# blackfin_a_sdram.net
KiCad netlist of a schematic drawn in Altium Designer
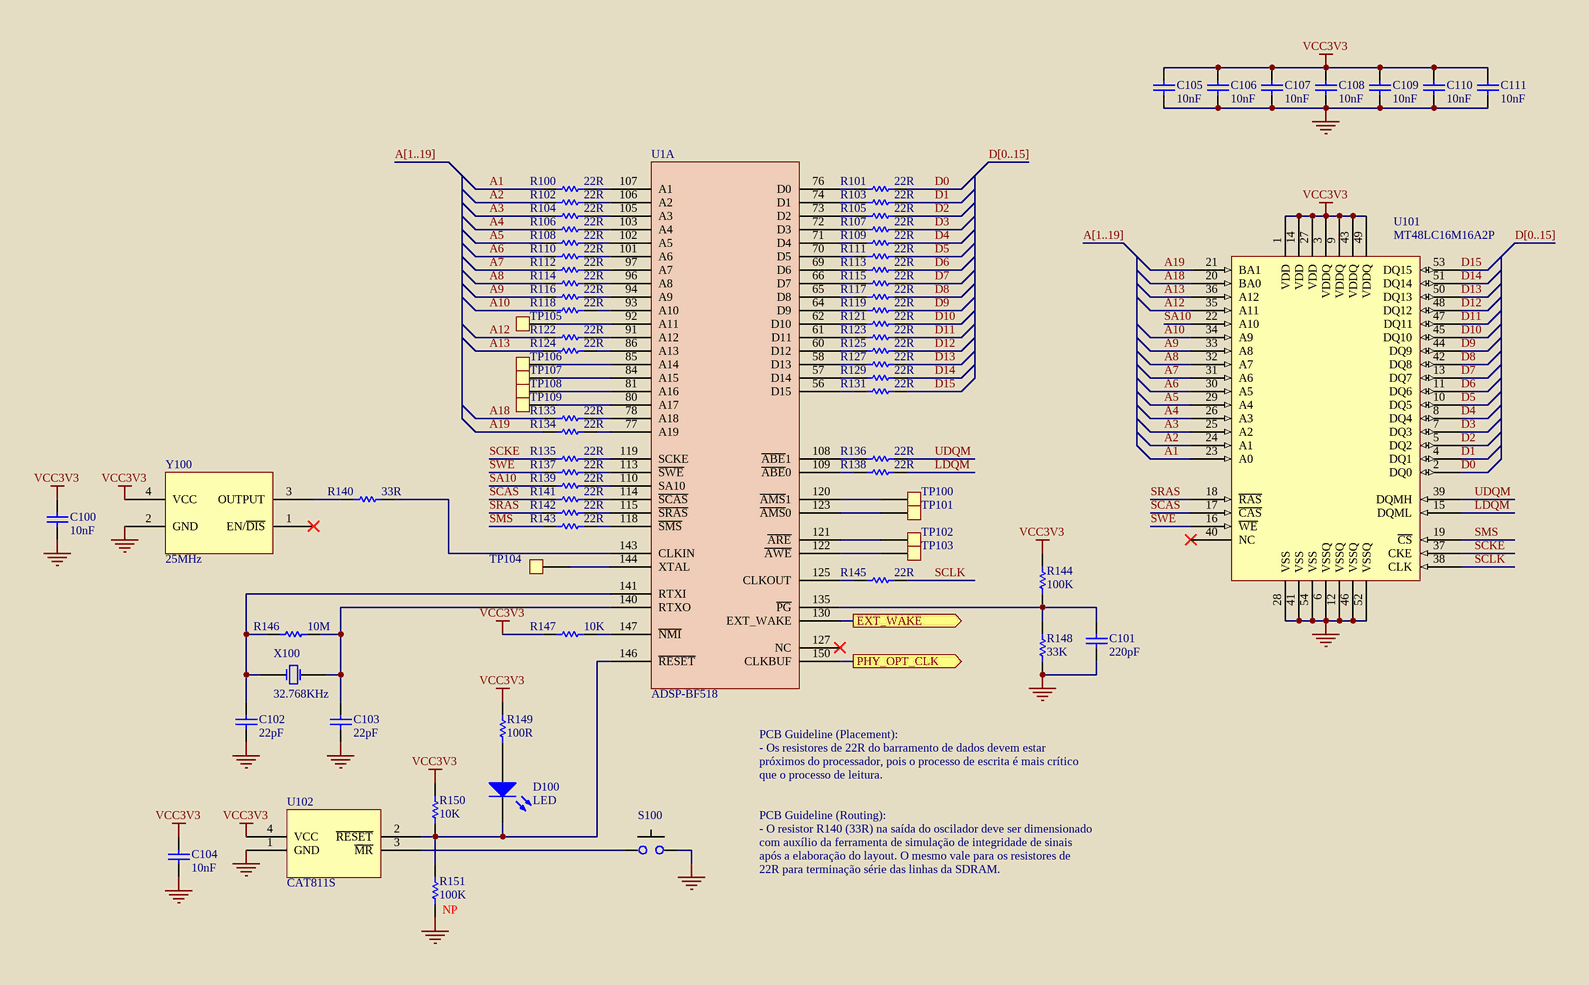
[diagram p0: blackfin_a_sdram.SchDoc]

(export (version "E")
  (design (tool "Eeschema 10.0.6"))
  (components
    (comp (ref "C100")
      (value "10nF")
      (footprint "blackfin_pcblib:C_0603")
      (fields
        (field (name "EVENDORPART#") "77-VJ0603Y103KXAPBC")
        (field (name "MANUFACTURER") "Vishay/Vitramon")
        (field (name "PART#") "VJ0603Y103KXAPW1BC")
      )
      (libsource (lib "blackfin_schlib") (part "Capacitor"))
    )
    (comp (ref "C101")
      (value "220pF")
      (footprint "blackfin_pcblib:C_0603")
      (fields
        (field (name "EVENDORPART#") "81-GRM18R72A221KA01D")
        (field (name "MANUFACTURER") "Murata")
        (field (name "PART#") "GRM188R72A221KA01D")
      )
      (libsource (lib "blackfin_schlib") (part "Capacitor"))
    )
    (comp (ref "C102")
      (value "22pF")
      (footprint "blackfin_pcblib:C_0603")
      (fields
        (field (name "EVENDORPART#") "581-06035A220J")
        (field (name "MANUFACTURER") "AVX")
        (field (name "PART#") "06035A220JAT2A")
      )
      (libsource (lib "blackfin_schlib") (part "Capacitor"))
    )
    (comp (ref "C103")
      (value "22pF")
      (footprint "blackfin_pcblib:C_0603")
      (fields
        (field (name "EVENDORPART#") "581-06035A220J")
        (field (name "MANUFACTURER") "AVX")
        (field (name "PART#") "06035A220JAT2A")
      )
      (libsource (lib "blackfin_schlib") (part "Capacitor"))
    )
    (comp (ref "C104")
      (value "10nF")
      (footprint "blackfin_pcblib:C_0603")
      (fields
        (field (name "EVENDORPART#") "77-VJ0603Y103KXAPBC")
        (field (name "MANUFACTURER") "Vishay/Vitramon")
        (field (name "PART#") "VJ0603Y103KXAPW1BC")
      )
      (libsource (lib "blackfin_schlib") (part "Capacitor"))
    )
    (comp (ref "C105")
      (value "10nF")
      (footprint "blackfin_pcblib:C_0603")
      (fields
        (field (name "EVENDORPART#") "77-VJ0603Y103KXAPBC")
        (field (name "MANUFACTURER") "Vishay/Vitramon")
        (field (name "PART#") "VJ0603Y103KXAPW1BC")
      )
      (libsource (lib "blackfin_schlib") (part "Capacitor"))
    )
    (comp (ref "C106")
      (value "10nF")
      (footprint "blackfin_pcblib:C_0603")
      (fields
        (field (name "EVENDORPART#") "77-VJ0603Y103KXAPBC")
        (field (name "MANUFACTURER") "Vishay/Vitramon")
        (field (name "PART#") "VJ0603Y103KXAPW1BC")
      )
      (libsource (lib "blackfin_schlib") (part "Capacitor"))
    )
    (comp (ref "C107")
      (value "10nF")
      (footprint "blackfin_pcblib:C_0603")
      (fields
        (field (name "EVENDORPART#") "77-VJ0603Y103KXAPBC")
        (field (name "MANUFACTURER") "Vishay/Vitramon")
        (field (name "PART#") "VJ0603Y103KXAPW1BC")
      )
      (libsource (lib "blackfin_schlib") (part "Capacitor"))
    )
    (comp (ref "C108")
      (value "10nF")
      (footprint "blackfin_pcblib:C_0603")
      (fields
        (field (name "EVENDORPART#") "77-VJ0603Y103KXAPBC")
        (field (name "MANUFACTURER") "Vishay/Vitramon")
        (field (name "PART#") "VJ0603Y103KXAPW1BC")
      )
      (libsource (lib "blackfin_schlib") (part "Capacitor"))
    )
    (comp (ref "C109")
      (value "10nF")
      (footprint "blackfin_pcblib:C_0603")
      (fields
        (field (name "EVENDORPART#") "77-VJ0603Y103KXAPBC")
        (field (name "MANUFACTURER") "Vishay/Vitramon")
        (field (name "PART#") "VJ0603Y103KXAPW1BC")
      )
      (libsource (lib "blackfin_schlib") (part "Capacitor"))
    )
    (comp (ref "C110")
      (value "10nF")
      (footprint "blackfin_pcblib:C_0603")
      (fields
        (field (name "EVENDORPART#") "77-VJ0603Y103KXAPBC")
        (field (name "MANUFACTURER") "Vishay/Vitramon")
        (field (name "PART#") "VJ0603Y103KXAPW1BC")
      )
      (libsource (lib "blackfin_schlib") (part "Capacitor"))
    )
    (comp (ref "C111")
      (value "10nF")
      (footprint "blackfin_pcblib:C_0603")
      (fields
        (field (name "EVENDORPART#") "77-VJ0603Y103KXAPBC")
        (field (name "MANUFACTURER") "Vishay/Vitramon")
        (field (name "PART#") "VJ0603Y103KXAPW1BC")
      )
      (libsource (lib "blackfin_schlib") (part "Capacitor"))
    )
    (comp (ref "D100")
      (value "LED")
      (footprint "blackfin_pcblib:LED_0603")
      (description "Red LED")
      (fields (field (name "EVENDORPART#") "638-QTLP600C2TR") (field (name "MANUFACTURER") "Everlight"))
      (libsource (lib "blackfin_schlib") (part "LED"))
    )
    (comp (ref "R100")
      (value "22R")
      (footprint "blackfin_pcblib:R_0402")
      (fields
        (field (name "EVENDORPART#") "71-CRCW0402J-22-E3")
        (field (name "PART#") "CRCW040222R0JNED")
        (field (name "MANUFACTURER") "Vishay/Dale")
      )
      (libsource (lib "blackfin_schlib") (part "Resistor"))
    )
    (comp (ref "R101")
      (value "22R")
      (footprint "blackfin_pcblib:R_0402")
      (fields
        (field (name "EVENDORPART#") "71-CRCW0402J-22-E3")
        (field (name "PART#") "CRCW040222R0JNED")
        (field (name "MANUFACTURER") "Vishay/Dale")
      )
      (libsource (lib "blackfin_schlib") (part "Resistor"))
    )
    (comp (ref "R102")
      (value "22R")
      (footprint "blackfin_pcblib:R_0402")
      (fields
        (field (name "EVENDORPART#") "71-CRCW0402J-22-E3")
        (field (name "PART#") "CRCW040222R0JNED")
        (field (name "MANUFACTURER") "Vishay/Dale")
      )
      (libsource (lib "blackfin_schlib") (part "Resistor"))
    )
    (comp (ref "R103")
      (value "22R")
      (footprint "blackfin_pcblib:R_0402")
      (fields
        (field (name "EVENDORPART#") "71-CRCW0402J-22-E3")
        (field (name "PART#") "CRCW040222R0JNED")
        (field (name "MANUFACTURER") "Vishay/Dale")
      )
      (libsource (lib "blackfin_schlib") (part "Resistor"))
    )
    (comp (ref "R104")
      (value "22R")
      (footprint "blackfin_pcblib:R_0402")
      (fields
        (field (name "EVENDORPART#") "71-CRCW0402J-22-E3")
        (field (name "PART#") "CRCW040222R0JNED")
        (field (name "MANUFACTURER") "Vishay/Dale")
      )
      (libsource (lib "blackfin_schlib") (part "Resistor"))
    )
    (comp (ref "R105")
      (value "22R")
      (footprint "blackfin_pcblib:R_0402")
      (fields
        (field (name "EVENDORPART#") "71-CRCW0402J-22-E3")
        (field (name "PART#") "CRCW040222R0JNED")
        (field (name "MANUFACTURER") "Vishay/Dale")
      )
      (libsource (lib "blackfin_schlib") (part "Resistor"))
    )
    (comp (ref "R106")
      (value "22R")
      (footprint "blackfin_pcblib:R_0402")
      (fields
        (field (name "EVENDORPART#") "71-CRCW0402J-22-E3")
        (field (name "PART#") "CRCW040222R0JNED")
        (field (name "MANUFACTURER") "Vishay/Dale")
      )
      (libsource (lib "blackfin_schlib") (part "Resistor"))
    )
    (comp (ref "R107")
      (value "22R")
      (footprint "blackfin_pcblib:R_0402")
      (fields
        (field (name "EVENDORPART#") "71-CRCW0402J-22-E3")
        (field (name "PART#") "CRCW040222R0JNED")
        (field (name "MANUFACTURER") "Vishay/Dale")
      )
      (libsource (lib "blackfin_schlib") (part "Resistor"))
    )
    (comp (ref "R108")
      (value "22R")
      (footprint "blackfin_pcblib:R_0402")
      (fields
        (field (name "EVENDORPART#") "71-CRCW0402J-22-E3")
        (field (name "PART#") "CRCW040222R0JNED")
        (field (name "MANUFACTURER") "Vishay/Dale")
      )
      (libsource (lib "blackfin_schlib") (part "Resistor"))
    )
    (comp (ref "R109")
      (value "22R")
      (footprint "blackfin_pcblib:R_0402")
      (fields
        (field (name "EVENDORPART#") "71-CRCW0402J-22-E3")
        (field (name "PART#") "CRCW040222R0JNED")
        (field (name "MANUFACTURER") "Vishay/Dale")
      )
      (libsource (lib "blackfin_schlib") (part "Resistor"))
    )
    (comp (ref "R110")
      (value "22R")
      (footprint "blackfin_pcblib:R_0402")
      (fields
        (field (name "EVENDORPART#") "71-CRCW0402J-22-E3")
        (field (name "PART#") "CRCW040222R0JNED")
        (field (name "MANUFACTURER") "Vishay/Dale")
      )
      (libsource (lib "blackfin_schlib") (part "Resistor"))
    )
    (comp (ref "R111")
      (value "22R")
      (footprint "blackfin_pcblib:R_0402")
      (fields
        (field (name "EVENDORPART#") "71-CRCW0402J-22-E3")
        (field (name "PART#") "CRCW040222R0JNED")
        (field (name "MANUFACTURER") "Vishay/Dale")
      )
      (libsource (lib "blackfin_schlib") (part "Resistor"))
    )
    (comp (ref "R112")
      (value "22R")
      (footprint "blackfin_pcblib:R_0402")
      (fields
        (field (name "EVENDORPART#") "71-CRCW0402J-22-E3")
        (field (name "PART#") "CRCW040222R0JNED")
        (field (name "MANUFACTURER") "Vishay/Dale")
      )
      (libsource (lib "blackfin_schlib") (part "Resistor"))
    )
    (comp (ref "R113")
      (value "22R")
      (footprint "blackfin_pcblib:R_0402")
      (fields
        (field (name "EVENDORPART#") "71-CRCW0402J-22-E3")
        (field (name "PART#") "CRCW040222R0JNED")
        (field (name "MANUFACTURER") "Vishay/Dale")
      )
      (libsource (lib "blackfin_schlib") (part "Resistor"))
    )
    (comp (ref "R114")
      (value "22R")
      (footprint "blackfin_pcblib:R_0402")
      (fields
        (field (name "EVENDORPART#") "71-CRCW0402J-22-E3")
        (field (name "PART#") "CRCW040222R0JNED")
        (field (name "MANUFACTURER") "Vishay/Dale")
      )
      (libsource (lib "blackfin_schlib") (part "Resistor"))
    )
    (comp (ref "R115")
      (value "22R")
      (footprint "blackfin_pcblib:R_0402")
      (fields
        (field (name "EVENDORPART#") "71-CRCW0402J-22-E3")
        (field (name "PART#") "CRCW040222R0JNED")
        (field (name "MANUFACTURER") "Vishay/Dale")
      )
      (libsource (lib "blackfin_schlib") (part "Resistor"))
    )
    (comp (ref "R116")
      (value "22R")
      (footprint "blackfin_pcblib:R_0402")
      (fields
        (field (name "EVENDORPART#") "71-CRCW0402J-22-E3")
        (field (name "PART#") "CRCW040222R0JNED")
        (field (name "MANUFACTURER") "Vishay/Dale")
      )
      (libsource (lib "blackfin_schlib") (part "Resistor"))
    )
    (comp (ref "R117")
      (value "22R")
      (footprint "blackfin_pcblib:R_0402")
      (fields
        (field (name "EVENDORPART#") "71-CRCW0402J-22-E3")
        (field (name "PART#") "CRCW040222R0JNED")
        (field (name "MANUFACTURER") "Vishay/Dale")
      )
      (libsource (lib "blackfin_schlib") (part "Resistor"))
    )
    (comp (ref "R118")
      (value "22R")
      (footprint "blackfin_pcblib:R_0402")
      (fields
        (field (name "EVENDORPART#") "71-CRCW0402J-22-E3")
        (field (name "PART#") "CRCW040222R0JNED")
        (field (name "MANUFACTURER") "Vishay/Dale")
      )
      (libsource (lib "blackfin_schlib") (part "Resistor"))
    )
    (comp (ref "R119")
      (value "22R")
      (footprint "blackfin_pcblib:R_0402")
      (fields
        (field (name "EVENDORPART#") "71-CRCW0402J-22-E3")
        (field (name "PART#") "CRCW040222R0JNED")
        (field (name "MANUFACTURER") "Vishay/Dale")
      )
      (libsource (lib "blackfin_schlib") (part "Resistor"))
    )
    (comp (ref "R121")
      (value "22R")
      (footprint "blackfin_pcblib:R_0402")
      (fields
        (field (name "EVENDORPART#") "71-CRCW0402J-22-E3")
        (field (name "PART#") "CRCW040222R0JNED")
        (field (name "MANUFACTURER") "Vishay/Dale")
      )
      (libsource (lib "blackfin_schlib") (part "Resistor"))
    )
    (comp (ref "R122")
      (value "22R")
      (footprint "blackfin_pcblib:R_0402")
      (fields
        (field (name "EVENDORPART#") "71-CRCW0402J-22-E3")
        (field (name "PART#") "CRCW040222R0JNED")
        (field (name "MANUFACTURER") "Vishay/Dale")
      )
      (libsource (lib "blackfin_schlib") (part "Resistor"))
    )
    (comp (ref "R123")
      (value "22R")
      (footprint "blackfin_pcblib:R_0402")
      (fields
        (field (name "EVENDORPART#") "71-CRCW0402J-22-E3")
        (field (name "PART#") "CRCW040222R0JNED")
        (field (name "MANUFACTURER") "Vishay/Dale")
      )
      (libsource (lib "blackfin_schlib") (part "Resistor"))
    )
    (comp (ref "R124")
      (value "22R")
      (footprint "blackfin_pcblib:R_0402")
      (fields
        (field (name "EVENDORPART#") "71-CRCW0402J-22-E3")
        (field (name "PART#") "CRCW040222R0JNED")
        (field (name "MANUFACTURER") "Vishay/Dale")
      )
      (libsource (lib "blackfin_schlib") (part "Resistor"))
    )
    (comp (ref "R125")
      (value "22R")
      (footprint "blackfin_pcblib:R_0402")
      (fields
        (field (name "EVENDORPART#") "71-CRCW0402J-22-E3")
        (field (name "PART#") "CRCW040222R0JNED")
        (field (name "MANUFACTURER") "Vishay/Dale")
      )
      (libsource (lib "blackfin_schlib") (part "Resistor"))
    )
    (comp (ref "R127")
      (value "22R")
      (footprint "blackfin_pcblib:R_0402")
      (fields
        (field (name "EVENDORPART#") "71-CRCW0402J-22-E3")
        (field (name "PART#") "CRCW040222R0JNED")
        (field (name "MANUFACTURER") "Vishay/Dale")
      )
      (libsource (lib "blackfin_schlib") (part "Resistor"))
    )
    (comp (ref "R129")
      (value "22R")
      (footprint "blackfin_pcblib:R_0402")
      (fields
        (field (name "EVENDORPART#") "71-CRCW0402J-22-E3")
        (field (name "PART#") "CRCW040222R0JNED")
        (field (name "MANUFACTURER") "Vishay/Dale")
      )
      (libsource (lib "blackfin_schlib") (part "Resistor"))
    )
    (comp (ref "R131")
      (value "22R")
      (footprint "blackfin_pcblib:R_0402")
      (fields
        (field (name "EVENDORPART#") "71-CRCW0402J-22-E3")
        (field (name "PART#") "CRCW040222R0JNED")
        (field (name "MANUFACTURER") "Vishay/Dale")
      )
      (libsource (lib "blackfin_schlib") (part "Resistor"))
    )
    (comp (ref "R133")
      (value "22R")
      (footprint "blackfin_pcblib:R_0402")
      (fields
        (field (name "EVENDORPART#") "71-CRCW0402J-22-E3")
        (field (name "PART#") "CRCW040222R0JNED")
        (field (name "MANUFACTURER") "Vishay/Dale")
      )
      (libsource (lib "blackfin_schlib") (part "Resistor"))
    )
    (comp (ref "R134")
      (value "22R")
      (footprint "blackfin_pcblib:R_0402")
      (fields
        (field (name "EVENDORPART#") "71-CRCW0402J-22-E3")
        (field (name "PART#") "CRCW040222R0JNED")
        (field (name "MANUFACTURER") "Vishay/Dale")
      )
      (libsource (lib "blackfin_schlib") (part "Resistor"))
    )
    (comp (ref "R135")
      (value "22R")
      (footprint "blackfin_pcblib:R_0402")
      (fields
        (field (name "EVENDORPART#") "71-CRCW0402J-22-E3")
        (field (name "PART#") "CRCW040222R0JNED")
        (field (name "MANUFACTURER") "Vishay/Dale")
      )
      (libsource (lib "blackfin_schlib") (part "Resistor"))
    )
    (comp (ref "R136")
      (value "22R")
      (footprint "blackfin_pcblib:R_0402")
      (fields
        (field (name "EVENDORPART#") "71-CRCW0402J-22-E3")
        (field (name "PART#") "CRCW040222R0JNED")
        (field (name "MANUFACTURER") "Vishay/Dale")
      )
      (libsource (lib "blackfin_schlib") (part "Resistor"))
    )
    (comp (ref "R137")
      (value "22R")
      (footprint "blackfin_pcblib:R_0402")
      (fields
        (field (name "EVENDORPART#") "71-CRCW0402J-22-E3")
        (field (name "PART#") "CRCW040222R0JNED")
        (field (name "MANUFACTURER") "Vishay/Dale")
      )
      (libsource (lib "blackfin_schlib") (part "Resistor"))
    )
    (comp (ref "R138")
      (value "22R")
      (footprint "blackfin_pcblib:R_0402")
      (fields
        (field (name "EVENDORPART#") "71-CRCW0402J-22-E3")
        (field (name "PART#") "CRCW040222R0JNED")
        (field (name "MANUFACTURER") "Vishay/Dale")
      )
      (libsource (lib "blackfin_schlib") (part "Resistor"))
    )
    (comp (ref "R139")
      (value "22R")
      (footprint "blackfin_pcblib:R_0402")
      (fields
        (field (name "EVENDORPART#") "71-CRCW0402J-22-E3")
        (field (name "PART#") "CRCW040222R0JNED")
        (field (name "MANUFACTURER") "Vishay/Dale")
      )
      (libsource (lib "blackfin_schlib") (part "Resistor"))
    )
    (comp (ref "R140")
      (value "33R")
      (footprint "blackfin_pcblib:R_0402")
      (fields
        (field (name "EVENDORPART#") "71-CRCW0402J-33-E3")
        (field (name "PART#") "CRCW040233R0JNED")
        (field (name "MANUFACTURER") "Vishay/Dale")
      )
      (libsource (lib "blackfin_schlib") (part "Resistor"))
    )
    (comp (ref "R141")
      (value "22R")
      (footprint "blackfin_pcblib:R_0402")
      (fields
        (field (name "EVENDORPART#") "71-CRCW0402J-22-E3")
        (field (name "PART#") "CRCW040222R0JNED")
        (field (name "MANUFACTURER") "Vishay/Dale")
      )
      (libsource (lib "blackfin_schlib") (part "Resistor"))
    )
    (comp (ref "R142")
      (value "22R")
      (footprint "blackfin_pcblib:R_0402")
      (fields
        (field (name "EVENDORPART#") "71-CRCW0402J-22-E3")
        (field (name "PART#") "CRCW040222R0JNED")
        (field (name "MANUFACTURER") "Vishay/Dale")
      )
      (libsource (lib "blackfin_schlib") (part "Resistor"))
    )
    (comp (ref "R143")
      (value "22R")
      (footprint "blackfin_pcblib:R_0402")
      (fields
        (field (name "EVENDORPART#") "71-CRCW0402J-22-E3")
        (field (name "PART#") "CRCW040222R0JNED")
        (field (name "MANUFACTURER") "Vishay/Dale")
      )
      (libsource (lib "blackfin_schlib") (part "Resistor"))
    )
    (comp (ref "R144")
      (value "100K")
      (footprint "blackfin_pcblib:R_0603")
      (fields
        (field (name "EVENDORPART#") "71-CRCW0603J-100K-E3")
        (field (name "PART#") "CRCW0603100KJNEA")
        (field (name "MANUFACTURER") "Vishay/Dale")
      )
      (libsource (lib "blackfin_schlib") (part "Resistor"))
    )
    (comp (ref "R145")
      (value "22R")
      (footprint "blackfin_pcblib:R_0402")
      (fields
        (field (name "EVENDORPART#") "71-CRCW0402J-22-E3")
        (field (name "PART#") "CRCW040222R0JNED")
        (field (name "MANUFACTURER") "Vishay/Dale")
      )
      (libsource (lib "blackfin_schlib") (part "Resistor"))
    )
    (comp (ref "R146")
      (value "10M")
      (footprint "blackfin_pcblib:R_0603")
      (fields
        (field (name "EVENDORPART#") "652-CR0603FX-1005ELF")
        (field (name "PART#") "CR0603-FX-1005ELF")
        (field (name "MANUFACTURER") "Bourns")
      )
      (libsource (lib "blackfin_schlib") (part "Resistor"))
    )
    (comp (ref "R147")
      (value "10K")
      (footprint "blackfin_pcblib:R_0603")
      (fields
        (field (name "EVENDORPART#") "71-CRCW0603-10K-E3")
        (field (name "PART#") "CRCW060310K0FKEA")
        (field (name "MANUFACTURER") "Vishay/Dale")
      )
      (libsource (lib "blackfin_schlib") (part "Resistor"))
    )
    (comp (ref "R148")
      (value "33K")
      (footprint "blackfin_pcblib:R_0603")
      (fields
        (field (name "EVENDORPART#") "71-CRCW0603J-33K-E3")
        (field (name "PART#") "CRCW060333K0JNEA")
        (field (name "MANUFACTURER") "Vishay/Dale")
      )
      (libsource (lib "blackfin_schlib") (part "Resistor"))
    )
    (comp (ref "R149")
      (value "100R")
      (footprint "blackfin_pcblib:R_0603")
      (fields
        (field (name "EVENDORPART#") "71-CRCW0603-100-E3")
        (field (name "PART#") "CRCW0603100RFKEA")
        (field (name "MANUFACTURER") "Vishay/Dale")
      )
      (libsource (lib "blackfin_schlib") (part "Resistor"))
    )
    (comp (ref "R150")
      (value "10K")
      (footprint "blackfin_pcblib:R_0603")
      (fields
        (field (name "EVENDORPART#") "71-CRCW0603-10K-E3")
        (field (name "PART#") "CRCW060310K0FKEA")
        (field (name "MANUFACTURER") "Vishay/Dale")
      )
      (libsource (lib "blackfin_schlib") (part "Resistor"))
    )
    (comp (ref "R151")
      (value "100K")
      (footprint "blackfin_pcblib:R_0603")
      (fields
        (field (name "EVENDORPART#") "71-CRCW0603J-100K-E3")
        (field (name "PART#") "CRCW0603100KJNEA")
        (field (name "MANUFACTURER") "Vishay/Dale")
      )
      (libsource (lib "blackfin_schlib") (part "Resistor"))
    )
    (comp (ref "S100")
      (value "Push Button")
      (footprint "blackfin_pcblib:Push Button")
      (fields
        (field (name "EVENDORPART#") "611-PTS645SH50SMTRLF")
        (field (name "PART#") "PTS645SH50SMTRLFS")
        (field (name "MANUFACTURER") "C&K Components")
      )
      (libsource (lib "*") (part "Push Button"))
    )
    (comp (ref "TP100")
      (value "Test Point")
      (footprint "blackfin_pcblib:Test Point")
      (fields (field (name "EVENDORPART#") "NÃO SE APLICA"))
      (libsource (lib "") (part "Test Point_1"))
    )
    (comp (ref "TP101")
      (value "Test Point")
      (footprint "blackfin_pcblib:Test Point")
      (fields (field (name "EVENDORPART#") "NÃO SE APLICA"))
      (libsource (lib "") (part "Test Point_1"))
    )
    (comp (ref "TP102")
      (value "Test Point")
      (footprint "blackfin_pcblib:Test Point")
      (fields (field (name "EVENDORPART#") "NÃO SE APLICA"))
      (libsource (lib "") (part "Test Point_1"))
    )
    (comp (ref "TP103")
      (value "Test Point")
      (footprint "blackfin_pcblib:Test Point")
      (fields (field (name "EVENDORPART#") "NÃO SE APLICA"))
      (libsource (lib "") (part "Test Point_1"))
    )
    (comp (ref "TP104")
      (value "Test Point")
      (footprint "blackfin_pcblib:Test Point")
      (fields (field (name "EVENDORPART#") "NÃO SE APLICA"))
      (libsource (lib "blackfin_schlib") (part "Test Point"))
    )
    (comp (ref "TP105")
      (value "Test Point")
      (footprint "blackfin_pcblib:Test Point")
      (fields (field (name "EVENDORPART#") "NÃO SE APLICA"))
      (libsource (lib "blackfin_schlib") (part "Test Point"))
    )
    (comp (ref "TP106")
      (value "Test Point")
      (footprint "blackfin_pcblib:Test Point")
      (fields (field (name "EVENDORPART#") "NÃO SE APLICA"))
      (libsource (lib "blackfin_schlib") (part "Test Point"))
    )
    (comp (ref "TP107")
      (value "Test Point")
      (footprint "blackfin_pcblib:Test Point")
      (fields (field (name "EVENDORPART#") "NÃO SE APLICA"))
      (libsource (lib "blackfin_schlib") (part "Test Point"))
    )
    (comp (ref "TP108")
      (value "Test Point")
      (footprint "blackfin_pcblib:Test Point")
      (fields (field (name "EVENDORPART#") "NÃO SE APLICA"))
      (libsource (lib "blackfin_schlib") (part "Test Point"))
    )
    (comp (ref "TP109")
      (value "Test Point")
      (footprint "blackfin_pcblib:Test Point")
      (fields (field (name "EVENDORPART#") "NÃO SE APLICA"))
      (libsource (lib "blackfin_schlib") (part "Test Point"))
    )
    (comp (ref "U1")
      (value "ADSP-BF518")
      (footprint "blackfin_pcblib:LQFP-176")
      (fields (field (name "EVENDORPART#") "ADSP-BF518BSWZ-4") (field (name "MANUFACTURER") "Analog Devices"))
      (libsource (lib "blackfin_schlib") (part "ADSP-BF518"))
    )
    (comp (ref "U101")
      (value "MT48LC16M16A2P")
      (footprint "blackfin_pcblib:TSOP-54")
      (fields
        (field (name "PART#") "MT48LC16M16A2P-75:D TR")
        (field (name "EVENDORPART#") "557-1059-1-ND")
        (field (name "MANUFACTURER") "Micron")
      )
      (libsource (lib "blackfin_schlib") (part "MT48LC16M16A2P"))
    )
    (comp (ref "U102")
      (value "CAT811S")
      (footprint "blackfin_pcblib:SOT-143")
      (fields
        (field (name "PART#") "CAT811STBI-GT3")
        (field (name "MANUFACTURER") "ON Semiconductor")
        (field (name "EVENDORPART#") "698-CAT811STBI-GT3")
      )
      (libsource (lib "*") (part "CAT811S"))
    )
    (comp (ref "X100")
      (value "32.768KHz")
      (footprint "blackfin_pcblib:XTAL_32.768kHz")
      (fields
        (field (name "EVENDORPART#") "SER2405CT-ND")
        (field (name "PART#") "MC-405")
        (field (name "MANUFACTURER") "Epson")
      )
      (libsource (lib "blackfin_schlib") (part "XTAL"))
    )
    (comp (ref "Y100")
      (value "25MHz")
      (footprint "blackfin_pcblib:OSC_25MHz")
      (fields
        (field (name "EVENDORPART#") "815-ASV-25-EJ-T")
        (field (name "PART#") "ASV-25.000MHZ-EJ-T")
        (field (name "MANUFACTURER") "ABRACON")
      )
      (libsource (lib "blackfin_schlib") (part "Oscillator_25MHz"))
    )
  )
  (nets
    (net (code "6") (name "/A1") (class "Default")
      (node (ref "R100") (pin "1") (pinfunction "1_1") (pintype "passive"))
      (node (ref "U101") (pin "23") (pinfunction "A0_23") (pintype "input"))
    )
    (net (code "7") (name "/A2") (class "Default")
      (node (ref "R102") (pin "1") (pinfunction "1_1") (pintype "passive"))
      (node (ref "U101") (pin "24") (pinfunction "A1_24") (pintype "input"))
    )
    (net (code "8") (name "/A3") (class "Default")
      (node (ref "R104") (pin "1") (pinfunction "1_1") (pintype "passive"))
      (node (ref "U101") (pin "25") (pinfunction "A2_25") (pintype "input"))
    )
    (net (code "9") (name "/A4") (class "Default")
      (node (ref "R106") (pin "1") (pinfunction "1_1") (pintype "passive"))
      (node (ref "U101") (pin "26") (pinfunction "A3_26") (pintype "input"))
    )
    (net (code "10") (name "/A5") (class "Default")
      (node (ref "R108") (pin "1") (pinfunction "1_1") (pintype "passive"))
      (node (ref "U101") (pin "29") (pinfunction "A4_29") (pintype "input"))
    )
    (net (code "11") (name "/A6") (class "Default")
      (node (ref "R110") (pin "1") (pinfunction "1_1") (pintype "passive"))
      (node (ref "U101") (pin "30") (pinfunction "A5_30") (pintype "input"))
    )
    (net (code "12") (name "/A7") (class "Default")
      (node (ref "R112") (pin "1") (pinfunction "1_1") (pintype "passive"))
      (node (ref "U101") (pin "31") (pinfunction "A6_31") (pintype "input"))
    )
    (net (code "13") (name "/A8") (class "Default")
      (node (ref "R114") (pin "1") (pinfunction "1_1") (pintype "passive"))
      (node (ref "U101") (pin "32") (pinfunction "A7_32") (pintype "input"))
    )
    (net (code "14") (name "/A9") (class "Default")
      (node (ref "R116") (pin "1") (pinfunction "1_1") (pintype "passive"))
      (node (ref "U101") (pin "33") (pinfunction "A8_33") (pintype "input"))
    )
    (net (code "15") (name "/A10") (class "Default")
      (node (ref "R118") (pin "1") (pinfunction "1_1") (pintype "passive"))
      (node (ref "U101") (pin "34") (pinfunction "A9_34") (pintype "input"))
    )
    (net (code "16") (name "/A12") (class "Default")
      (node (ref "R122") (pin "1") (pinfunction "1_1") (pintype "passive"))
      (node (ref "U101") (pin "35") (pinfunction "A11_35") (pintype "input"))
    )
    (net (code "17") (name "/A13") (class "Default")
      (node (ref "R124") (pin "1") (pinfunction "1_1") (pintype "passive"))
      (node (ref "U101") (pin "36") (pinfunction "A12_36") (pintype "input"))
    )
    (net (code "18") (name "/A18") (class "Default")
      (node (ref "R133") (pin "1") (pinfunction "1_1") (pintype "passive"))
      (node (ref "U101") (pin "20") (pinfunction "BA0_20") (pintype "input"))
    )
    (net (code "19") (name "/A19") (class "Default")
      (node (ref "R134") (pin "1") (pinfunction "1_1") (pintype "passive"))
      (node (ref "U101") (pin "21") (pinfunction "BA1_21") (pintype "input"))
    )
    (net (code "21") (name "/D0") (class "Default")
      (node (ref "R101") (pin "2") (pinfunction "2_2") (pintype "passive"))
      (node (ref "U101") (pin "2") (pinfunction "DQ0_2") (pintype "bidirectional"))
    )
    (net (code "22") (name "/D1") (class "Default")
      (node (ref "R103") (pin "2") (pinfunction "2_2") (pintype "passive"))
      (node (ref "U101") (pin "4") (pinfunction "DQ1_4") (pintype "bidirectional"))
    )
    (net (code "23") (name "/D2") (class "Default")
      (node (ref "R105") (pin "2") (pinfunction "2_2") (pintype "passive"))
      (node (ref "U101") (pin "5") (pinfunction "DQ2_5") (pintype "bidirectional"))
    )
    (net (code "24") (name "/D3") (class "Default")
      (node (ref "R107") (pin "2") (pinfunction "2_2") (pintype "passive"))
      (node (ref "U101") (pin "7") (pinfunction "DQ3_7") (pintype "bidirectional"))
    )
    (net (code "25") (name "/D4") (class "Default")
      (node (ref "R109") (pin "2") (pinfunction "2_2") (pintype "passive"))
      (node (ref "U101") (pin "8") (pinfunction "DQ4_8") (pintype "bidirectional"))
    )
    (net (code "26") (name "/D5") (class "Default")
      (node (ref "R111") (pin "2") (pinfunction "2_2") (pintype "passive"))
      (node (ref "U101") (pin "10") (pinfunction "DQ5_10") (pintype "bidirectional"))
    )
    (net (code "27") (name "/D6") (class "Default")
      (node (ref "R113") (pin "2") (pinfunction "2_2") (pintype "passive"))
      (node (ref "U101") (pin "11") (pinfunction "DQ6_11") (pintype "bidirectional"))
    )
    (net (code "28") (name "/D7") (class "Default")
      (node (ref "R115") (pin "2") (pinfunction "2_2") (pintype "passive"))
      (node (ref "U101") (pin "13") (pinfunction "DQ7_13") (pintype "bidirectional"))
    )
    (net (code "29") (name "/D8") (class "Default")
      (node (ref "R117") (pin "2") (pinfunction "2_2") (pintype "passive"))
      (node (ref "U101") (pin "42") (pinfunction "DQ8_42") (pintype "bidirectional"))
    )
    (net (code "30") (name "/D9") (class "Default")
      (node (ref "R119") (pin "2") (pinfunction "2_2") (pintype "passive"))
      (node (ref "U101") (pin "44") (pinfunction "DQ9_44") (pintype "bidirectional"))
    )
    (net (code "31") (name "/D10") (class "Default")
      (node (ref "R121") (pin "2") (pinfunction "2_2") (pintype "passive"))
      (node (ref "U101") (pin "45") (pinfunction "DQ10_45") (pintype "bidirectional"))
    )
    (net (code "32") (name "/D11") (class "Default")
      (node (ref "R123") (pin "2") (pinfunction "2_2") (pintype "passive"))
      (node (ref "U101") (pin "47") (pinfunction "DQ11_47") (pintype "bidirectional"))
    )
    (net (code "33") (name "/D12") (class "Default")
      (node (ref "R125") (pin "2") (pinfunction "2_2") (pintype "passive"))
      (node (ref "U101") (pin "48") (pinfunction "DQ12_48") (pintype "bidirectional"))
    )
    (net (code "34") (name "/D13") (class "Default")
      (node (ref "R127") (pin "2") (pinfunction "2_2") (pintype "passive"))
      (node (ref "U101") (pin "50") (pinfunction "DQ13_50") (pintype "bidirectional"))
    )
    (net (code "35") (name "/D14") (class "Default")
      (node (ref "R129") (pin "2") (pinfunction "2_2") (pintype "passive"))
      (node (ref "U101") (pin "51") (pinfunction "DQ14_51") (pintype "bidirectional"))
    )
    (net (code "36") (name "/D15") (class "Default")
      (node (ref "R131") (pin "2") (pinfunction "2_2") (pintype "passive"))
      (node (ref "U101") (pin "53") (pinfunction "DQ15_53") (pintype "bidirectional"))
    )
    (net (code "38") (name "/EXT_WAKE") (class "Default")
      (node (ref "U1") (pin "130") (pinfunction "EXT_WAKE_130") (pintype "passive"))
    )
    (net (code "39") (name "/LDQM") (class "Default")
      (node (ref "R138") (pin "2") (pinfunction "2_2") (pintype "passive"))
      (node (ref "U101") (pin "15") (pinfunction "DQML_15") (pintype "input"))
    )
    (net (code "40") (name "/PHY_OPT_CLK") (class "Default")
      (node (ref "U1") (pin "150") (pinfunction "CLKBUF_150") (pintype "passive"))
    )
    (net (code "41") (name "/SA10") (class "Default")
      (node (ref "R139") (pin "1") (pinfunction "1_1") (pintype "passive"))
      (node (ref "U101") (pin "22") (pinfunction "A10_22") (pintype "input"))
    )
    (net (code "42") (name "/SCAS") (class "Default")
      (node (ref "R141") (pin "1") (pinfunction "1_1") (pintype "passive"))
      (node (ref "U101") (pin "17") (pinfunction "~{CAS}_17") (pintype "input"))
    )
    (net (code "43") (name "/SCKE") (class "Default")
      (node (ref "R135") (pin "1") (pinfunction "1_1") (pintype "passive"))
      (node (ref "U101") (pin "37") (pinfunction "CKE_37") (pintype "input"))
    )
    (net (code "44") (name "/SCLK") (class "Default")
      (node (ref "R145") (pin "2") (pinfunction "2_2") (pintype "passive"))
      (node (ref "U101") (pin "38") (pinfunction "CLK_38") (pintype "input"))
    )
    (net (code "45") (name "/SMS") (class "Default")
      (node (ref "R143") (pin "1") (pinfunction "1_1") (pintype "passive"))
      (node (ref "U101") (pin "19") (pinfunction "~{CS}_19") (pintype "input"))
    )
    (net (code "46") (name "/SRAS") (class "Default")
      (node (ref "R142") (pin "1") (pinfunction "1_1") (pintype "passive"))
      (node (ref "U101") (pin "18") (pinfunction "~{RAS}_18") (pintype "input"))
    )
    (net (code "47") (name "/SWE") (class "Default")
      (node (ref "R137") (pin "1") (pinfunction "1_1") (pintype "passive"))
      (node (ref "U101") (pin "16") (pinfunction "~{WE}_16") (pintype "input"))
    )
    (net (code "48") (name "/UDQM") (class "Default")
      (node (ref "R136") (pin "2") (pinfunction "2_2") (pintype "passive"))
      (node (ref "U101") (pin "39") (pinfunction "DQMH_39") (pintype "input"))
    )
    (net (code "49") (name "GND") (class "Default")
      (node (ref "C100") (pin "1") (pinfunction "1_1") (pintype "passive"))
      (node (ref "C101") (pin "1") (pinfunction "1_1") (pintype "passive"))
      (node (ref "C102") (pin "1") (pinfunction "1_1") (pintype "passive"))
      (node (ref "C103") (pin "1") (pinfunction "1_1") (pintype "passive"))
      (node (ref "C104") (pin "1") (pinfunction "1_1") (pintype "passive"))
      (node (ref "C105") (pin "1") (pinfunction "1_1") (pintype "passive"))
      (node (ref "C106") (pin "1") (pinfunction "1_1") (pintype "passive"))
      (node (ref "C107") (pin "1") (pinfunction "1_1") (pintype "passive"))
      (node (ref "C108") (pin "1") (pinfunction "1_1") (pintype "passive"))
      (node (ref "C109") (pin "1") (pinfunction "1_1") (pintype "passive"))
      (node (ref "C110") (pin "1") (pinfunction "1_1") (pintype "passive"))
      (node (ref "C111") (pin "1") (pinfunction "1_1") (pintype "passive"))
      (node (ref "R148") (pin "1") (pinfunction "1_1") (pintype "passive"))
      (node (ref "R151") (pin "1") (pinfunction "1_1") (pintype "passive"))
      (node (ref "S100") (pin "2") (pinfunction "2_2") (pintype "passive"))
      (node (ref "U101") (pin "12") (pinfunction "VSSQ_12") (pintype "power_in"))
      (node (ref "U101") (pin "28") (pinfunction "VSS_28") (pintype "power_in"))
      (node (ref "U101") (pin "41") (pinfunction "VSS_41") (pintype "power_in"))
      (node (ref "U101") (pin "46") (pinfunction "VSSQ_46") (pintype "power_in"))
      (node (ref "U101") (pin "52") (pinfunction "VSSQ_52") (pintype "power_in"))
      (node (ref "U101") (pin "54") (pinfunction "VSS_54") (pintype "power_in"))
      (node (ref "U101") (pin "6") (pinfunction "VSSQ_6") (pintype "power_in"))
      (node (ref "U102") (pin "1") (pinfunction "GND_1") (pintype "passive"))
      (node (ref "Y100") (pin "2") (pinfunction "GND_2") (pintype "passive"))
    )
    (net (code "50") (name "Net-(D100-A)") (class "Default")
      (node (ref "D100") (pin "1") (pinfunction "A_1") (pintype "passive"))
      (node (ref "R149") (pin "1") (pinfunction "1_1") (pintype "passive"))
    )
    (net (code "51") (name "Net-(D100-K)") (class "Default")
      (node (ref "D100") (pin "2") (pinfunction "K_2") (pintype "passive"))
      (node (ref "R150") (pin "2") (pinfunction "2_2") (pintype "passive"))
      (node (ref "R151") (pin "2") (pinfunction "2_2") (pintype "passive"))
      (node (ref "U1") (pin "146") (pinfunction "~{RESET}_146") (pintype "passive"))
      (node (ref "U102") (pin "2") (pinfunction "~{RESET}_2") (pintype "passive"))
    )
    (net (code "52") (name "Net-(U1A-A1)") (class "Default")
      (node (ref "R100") (pin "2") (pinfunction "2_2") (pintype "passive"))
      (node (ref "U1") (pin "107") (pinfunction "A1_107") (pintype "passive"))
    )
    (net (code "53") (name "Net-(U1A-A2)") (class "Default")
      (node (ref "R102") (pin "2") (pinfunction "2_2") (pintype "passive"))
      (node (ref "U1") (pin "106") (pinfunction "A2_106") (pintype "passive"))
    )
    (net (code "54") (name "Net-(U1A-A3)") (class "Default")
      (node (ref "R104") (pin "2") (pinfunction "2_2") (pintype "passive"))
      (node (ref "U1") (pin "105") (pinfunction "A3_105") (pintype "passive"))
    )
    (net (code "55") (name "Net-(U1A-A4)") (class "Default")
      (node (ref "R106") (pin "2") (pinfunction "2_2") (pintype "passive"))
      (node (ref "U1") (pin "103") (pinfunction "A4_103") (pintype "passive"))
    )
    (net (code "56") (name "Net-(U1A-A5)") (class "Default")
      (node (ref "R108") (pin "2") (pinfunction "2_2") (pintype "passive"))
      (node (ref "U1") (pin "102") (pinfunction "A5_102") (pintype "passive"))
    )
    (net (code "57") (name "Net-(U1A-A6)") (class "Default")
      (node (ref "R110") (pin "2") (pinfunction "2_2") (pintype "passive"))
      (node (ref "U1") (pin "101") (pinfunction "A6_101") (pintype "passive"))
    )
    (net (code "58") (name "Net-(U1A-A7)") (class "Default")
      (node (ref "R112") (pin "2") (pinfunction "2_2") (pintype "passive"))
      (node (ref "U1") (pin "97") (pinfunction "A7_97") (pintype "passive"))
    )
    (net (code "59") (name "Net-(U1A-A8)") (class "Default")
      (node (ref "R114") (pin "2") (pinfunction "2_2") (pintype "passive"))
      (node (ref "U1") (pin "96") (pinfunction "A8_96") (pintype "passive"))
    )
    (net (code "60") (name "Net-(U1A-A9)") (class "Default")
      (node (ref "R116") (pin "2") (pinfunction "2_2") (pintype "passive"))
      (node (ref "U1") (pin "94") (pinfunction "A9_94") (pintype "passive"))
    )
    (net (code "61") (name "Net-(U1A-A10)") (class "Default")
      (node (ref "R118") (pin "2") (pinfunction "2_2") (pintype "passive"))
      (node (ref "U1") (pin "93") (pinfunction "A10_93") (pintype "passive"))
    )
    (net (code "62") (name "Net-(U1A-A11)") (class "Default")
      (node (ref "TP105") (pin "1") (pinfunction "1_1") (pintype "passive"))
      (node (ref "U1") (pin "92") (pinfunction "A11_92") (pintype "passive"))
    )
    (net (code "63") (name "Net-(U1A-A12)") (class "Default")
      (node (ref "R122") (pin "2") (pinfunction "2_2") (pintype "passive"))
      (node (ref "U1") (pin "91") (pinfunction "A12_91") (pintype "passive"))
    )
    (net (code "64") (name "Net-(U1A-A13)") (class "Default")
      (node (ref "R124") (pin "2") (pinfunction "2_2") (pintype "passive"))
      (node (ref "U1") (pin "86") (pinfunction "A13_86") (pintype "passive"))
    )
    (net (code "65") (name "Net-(U1A-A14)") (class "Default")
      (node (ref "TP106") (pin "1") (pinfunction "1_1") (pintype "passive"))
      (node (ref "U1") (pin "85") (pinfunction "A14_85") (pintype "passive"))
    )
    (net (code "66") (name "Net-(U1A-A15)") (class "Default")
      (node (ref "TP107") (pin "1") (pinfunction "1_1") (pintype "passive"))
      (node (ref "U1") (pin "84") (pinfunction "A15_84") (pintype "passive"))
    )
    (net (code "67") (name "Net-(U1A-A16)") (class "Default")
      (node (ref "TP108") (pin "1") (pinfunction "1_1") (pintype "passive"))
      (node (ref "U1") (pin "81") (pinfunction "A16_81") (pintype "passive"))
    )
    (net (code "68") (name "Net-(U1A-A17)") (class "Default")
      (node (ref "TP109") (pin "1") (pinfunction "1_1") (pintype "passive"))
      (node (ref "U1") (pin "80") (pinfunction "A17_80") (pintype "passive"))
    )
    (net (code "69") (name "Net-(U1A-A18)") (class "Default")
      (node (ref "R133") (pin "2") (pinfunction "2_2") (pintype "passive"))
      (node (ref "U1") (pin "78") (pinfunction "A18_78") (pintype "passive"))
    )
    (net (code "70") (name "Net-(U1A-A19)") (class "Default")
      (node (ref "R134") (pin "2") (pinfunction "2_2") (pintype "passive"))
      (node (ref "U1") (pin "77") (pinfunction "A19_77") (pintype "passive"))
    )
    (net (code "71") (name "Net-(U1A-CLKIN)") (class "Default")
      (node (ref "R140") (pin "2") (pinfunction "2_2") (pintype "passive"))
      (node (ref "U1") (pin "143") (pinfunction "CLKIN_143") (pintype "passive"))
    )
    (net (code "72") (name "Net-(U1A-CLKOUT)") (class "Default")
      (node (ref "R145") (pin "1") (pinfunction "1_1") (pintype "passive"))
      (node (ref "U1") (pin "125") (pinfunction "CLKOUT_125") (pintype "passive"))
    )
    (net (code "73") (name "Net-(U1A-D0)") (class "Default")
      (node (ref "R101") (pin "1") (pinfunction "1_1") (pintype "passive"))
      (node (ref "U1") (pin "76") (pinfunction "D0_76") (pintype "passive"))
    )
    (net (code "74") (name "Net-(U1A-D1)") (class "Default")
      (node (ref "R103") (pin "1") (pinfunction "1_1") (pintype "passive"))
      (node (ref "U1") (pin "74") (pinfunction "D1_74") (pintype "passive"))
    )
    (net (code "75") (name "Net-(U1A-D2)") (class "Default")
      (node (ref "R105") (pin "1") (pinfunction "1_1") (pintype "passive"))
      (node (ref "U1") (pin "73") (pinfunction "D2_73") (pintype "passive"))
    )
    (net (code "76") (name "Net-(U1A-D3)") (class "Default")
      (node (ref "R107") (pin "1") (pinfunction "1_1") (pintype "passive"))
      (node (ref "U1") (pin "72") (pinfunction "D3_72") (pintype "passive"))
    )
    (net (code "77") (name "Net-(U1A-D4)") (class "Default")
      (node (ref "R109") (pin "1") (pinfunction "1_1") (pintype "passive"))
      (node (ref "U1") (pin "71") (pinfunction "D4_71") (pintype "passive"))
    )
    (net (code "78") (name "Net-(U1A-D5)") (class "Default")
      (node (ref "R111") (pin "1") (pinfunction "1_1") (pintype "passive"))
      (node (ref "U1") (pin "70") (pinfunction "D5_70") (pintype "passive"))
    )
    (net (code "79") (name "Net-(U1A-D6)") (class "Default")
      (node (ref "R113") (pin "1") (pinfunction "1_1") (pintype "passive"))
      (node (ref "U1") (pin "69") (pinfunction "D6_69") (pintype "passive"))
    )
    (net (code "80") (name "Net-(U1A-D7)") (class "Default")
      (node (ref "R115") (pin "1") (pinfunction "1_1") (pintype "passive"))
      (node (ref "U1") (pin "66") (pinfunction "D7_66") (pintype "passive"))
    )
    (net (code "81") (name "Net-(U1A-D8)") (class "Default")
      (node (ref "R117") (pin "1") (pinfunction "1_1") (pintype "passive"))
      (node (ref "U1") (pin "65") (pinfunction "D8_65") (pintype "passive"))
    )
    (net (code "82") (name "Net-(U1A-D9)") (class "Default")
      (node (ref "R119") (pin "1") (pinfunction "1_1") (pintype "passive"))
      (node (ref "U1") (pin "64") (pinfunction "D9_64") (pintype "passive"))
    )
    (net (code "83") (name "Net-(U1A-D10)") (class "Default")
      (node (ref "R121") (pin "1") (pinfunction "1_1") (pintype "passive"))
      (node (ref "U1") (pin "62") (pinfunction "D10_62") (pintype "passive"))
    )
    (net (code "84") (name "Net-(U1A-D11)") (class "Default")
      (node (ref "R123") (pin "1") (pinfunction "1_1") (pintype "passive"))
      (node (ref "U1") (pin "61") (pinfunction "D11_61") (pintype "passive"))
    )
    (net (code "85") (name "Net-(U1A-D12)") (class "Default")
      (node (ref "R125") (pin "1") (pinfunction "1_1") (pintype "passive"))
      (node (ref "U1") (pin "60") (pinfunction "D12_60") (pintype "passive"))
    )
    (net (code "86") (name "Net-(U1A-D13)") (class "Default")
      (node (ref "R127") (pin "1") (pinfunction "1_1") (pintype "passive"))
      (node (ref "U1") (pin "58") (pinfunction "D13_58") (pintype "passive"))
    )
    (net (code "87") (name "Net-(U1A-D14)") (class "Default")
      (node (ref "R129") (pin "1") (pinfunction "1_1") (pintype "passive"))
      (node (ref "U1") (pin "57") (pinfunction "D14_57") (pintype "passive"))
    )
    (net (code "88") (name "Net-(U1A-D15)") (class "Default")
      (node (ref "R131") (pin "1") (pinfunction "1_1") (pintype "passive"))
      (node (ref "U1") (pin "56") (pinfunction "D15_56") (pintype "passive"))
    )
    (net (code "89") (name "Net-(U1A-RTXI)") (class "Default")
      (node (ref "C102") (pin "2") (pinfunction "2_2") (pintype "passive"))
      (node (ref "R146") (pin "1") (pinfunction "1_1") (pintype "passive"))
      (node (ref "U1") (pin "141") (pinfunction "RTXI_141") (pintype "passive"))
      (node (ref "X100") (pin "1") (pinfunction "OSC1_1") (pintype "passive"))
    )
    (net (code "90") (name "Net-(U1A-RTXO)") (class "Default")
      (node (ref "C103") (pin "2") (pinfunction "2_2") (pintype "passive"))
      (node (ref "R146") (pin "2") (pinfunction "2_2") (pintype "passive"))
      (node (ref "U1") (pin "140") (pinfunction "RTXO_140") (pintype "passive"))
      (node (ref "X100") (pin "2") (pinfunction "OSC2_2") (pintype "passive"))
    )
    (net (code "91") (name "Net-(U1A-SA10)") (class "Default")
      (node (ref "R139") (pin "2") (pinfunction "2_2") (pintype "passive"))
      (node (ref "U1") (pin "110") (pinfunction "SA10_110") (pintype "passive"))
    )
    (net (code "92") (name "Net-(U1A-SCKE)") (class "Default")
      (node (ref "R135") (pin "2") (pinfunction "2_2") (pintype "passive"))
      (node (ref "U1") (pin "119") (pinfunction "SCKE_119") (pintype "passive"))
    )
    (net (code "93") (name "Net-(U1A-XTAL)") (class "Default")
      (node (ref "TP104") (pin "1") (pinfunction "1_1") (pintype "passive"))
      (node (ref "U1") (pin "144") (pinfunction "XTAL_144") (pintype "passive"))
    )
    (net (code "94") (name "Net-(U1A-~{ABE}0)") (class "Default")
      (node (ref "R138") (pin "1") (pinfunction "1_1") (pintype "passive"))
      (node (ref "U1") (pin "109") (pinfunction "~{ABE}0_109") (pintype "passive"))
    )
    (net (code "95") (name "Net-(U1A-~{ABE}1)") (class "Default")
      (node (ref "R136") (pin "1") (pinfunction "1_1") (pintype "passive"))
      (node (ref "U1") (pin "108") (pinfunction "~{ABE}1_108") (pintype "passive"))
    )
    (net (code "96") (name "Net-(U1A-~{AMS}0)") (class "Default")
      (node (ref "TP101") (pin "1") (pinfunction "1_1") (pintype "passive"))
      (node (ref "U1") (pin "123") (pinfunction "~{AMS}0_123") (pintype "passive"))
    )
    (net (code "97") (name "Net-(U1A-~{AMS}1)") (class "Default")
      (node (ref "TP100") (pin "1") (pinfunction "1_1") (pintype "passive"))
      (node (ref "U1") (pin "120") (pinfunction "~{AMS}1_120") (pintype "passive"))
    )
    (net (code "98") (name "Net-(U1A-~{ARE})") (class "Default")
      (node (ref "TP102") (pin "1") (pinfunction "1_1") (pintype "passive"))
      (node (ref "U1") (pin "121") (pinfunction "~{ARE}_121") (pintype "passive"))
    )
    (net (code "99") (name "Net-(U1A-~{AWE})") (class "Default")
      (node (ref "TP103") (pin "1") (pinfunction "1_1") (pintype "passive"))
      (node (ref "U1") (pin "122") (pinfunction "~{AWE}_122") (pintype "passive"))
    )
    (net (code "100") (name "Net-(U1A-~{NMI})") (class "Default")
      (node (ref "R147") (pin "1") (pinfunction "1_1") (pintype "passive"))
      (node (ref "U1") (pin "147") (pinfunction "~{NMI}_147") (pintype "passive"))
    )
    (net (code "101") (name "Net-(U1A-~{PG})") (class "Default")
      (node (ref "C101") (pin "2") (pinfunction "2_2") (pintype "passive"))
      (node (ref "R144") (pin "1") (pinfunction "1_1") (pintype "passive"))
      (node (ref "R148") (pin "2") (pinfunction "2_2") (pintype "passive"))
      (node (ref "U1") (pin "135") (pinfunction "~{PG}_135") (pintype "passive"))
    )
    (net (code "102") (name "Net-(U1A-~{SCAS})") (class "Default")
      (node (ref "R141") (pin "2") (pinfunction "2_2") (pintype "passive"))
      (node (ref "U1") (pin "114") (pinfunction "~{SCAS}_114") (pintype "passive"))
    )
    (net (code "103") (name "Net-(U1A-~{SMS})") (class "Default")
      (node (ref "R143") (pin "2") (pinfunction "2_2") (pintype "passive"))
      (node (ref "U1") (pin "118") (pinfunction "~{SMS}_118") (pintype "passive"))
    )
    (net (code "104") (name "Net-(U1A-~{SRAS})") (class "Default")
      (node (ref "R142") (pin "2") (pinfunction "2_2") (pintype "passive"))
      (node (ref "U1") (pin "115") (pinfunction "~{SRAS}_115") (pintype "passive"))
    )
    (net (code "105") (name "Net-(U1A-~{SWE})") (class "Default")
      (node (ref "R137") (pin "2") (pinfunction "2_2") (pintype "passive"))
      (node (ref "U1") (pin "113") (pinfunction "~{SWE}_113") (pintype "passive"))
    )
    (net (code "106") (name "Net-(U102-~{MR})") (class "Default")
      (node (ref "S100") (pin "1") (pinfunction "1_1") (pintype "passive"))
      (node (ref "U102") (pin "3") (pinfunction "~{MR}_3") (pintype "passive"))
    )
    (net (code "107") (name "Net-(Y100-OUTPUT)") (class "Default")
      (node (ref "R140") (pin "1") (pinfunction "1_1") (pintype "passive"))
      (node (ref "Y100") (pin "3") (pinfunction "OUTPUT_3") (pintype "passive"))
    )
    (net (code "108") (name "VCC3V3") (class "Default")
      (node (ref "C100") (pin "2") (pinfunction "2_2") (pintype "passive"))
      (node (ref "C104") (pin "2") (pinfunction "2_2") (pintype "passive"))
      (node (ref "C105") (pin "2") (pinfunction "2_2") (pintype "passive"))
      (node (ref "C106") (pin "2") (pinfunction "2_2") (pintype "passive"))
      (node (ref "C107") (pin "2") (pinfunction "2_2") (pintype "passive"))
      (node (ref "C108") (pin "2") (pinfunction "2_2") (pintype "passive"))
      (node (ref "C109") (pin "2") (pinfunction "2_2") (pintype "passive"))
      (node (ref "C110") (pin "2") (pinfunction "2_2") (pintype "passive"))
      (node (ref "C111") (pin "2") (pinfunction "2_2") (pintype "passive"))
      (node (ref "R144") (pin "2") (pinfunction "2_2") (pintype "passive"))
      (node (ref "R147") (pin "2") (pinfunction "2_2") (pintype "passive"))
      (node (ref "R149") (pin "2") (pinfunction "2_2") (pintype "passive"))
      (node (ref "R150") (pin "1") (pinfunction "1_1") (pintype "passive"))
      (node (ref "U101") (pin "1") (pinfunction "VDD_1") (pintype "power_in"))
      (node (ref "U101") (pin "14") (pinfunction "VDD_14") (pintype "power_in"))
      (node (ref "U101") (pin "27") (pinfunction "VDD_27") (pintype "power_in"))
      (node (ref "U101") (pin "3") (pinfunction "VDDQ_3") (pintype "power_in"))
      (node (ref "U101") (pin "43") (pinfunction "VDDQ_43") (pintype "power_in"))
      (node (ref "U101") (pin "49") (pinfunction "VDDQ_49") (pintype "power_in"))
      (node (ref "U101") (pin "9") (pinfunction "VDDQ_9") (pintype "power_in"))
      (node (ref "U102") (pin "4") (pinfunction "VCC_4") (pintype "passive"))
      (node (ref "Y100") (pin "4") (pinfunction "VCC_4") (pintype "passive"))
    )
    (net (code "109") (name "unconnected-(U1A-NC-Pad127)") (class "Default")
      (node (ref "U1") (pin "127") (pinfunction "NC_127") (pintype "passive+no_connect"))
    )
    (net (code "110") (name "unconnected-(U101-NC-Pad40)") (class "Default")
      (node (ref "U101") (pin "40") (pinfunction "NC_40") (pintype "passive+no_connect"))
    )
    (net (code "111") (name "unconnected-(Y100-EN{slash}~{DIS}-Pad1)") (class "Default")
      (node (ref "Y100") (pin "1") (pinfunction "EN/~{DIS}_1") (pintype "passive+no_connect"))
    )
  )
)
